# 03-_Power_Decoupling.net
KiCad netlist of a schematic drawn in Altium Designer
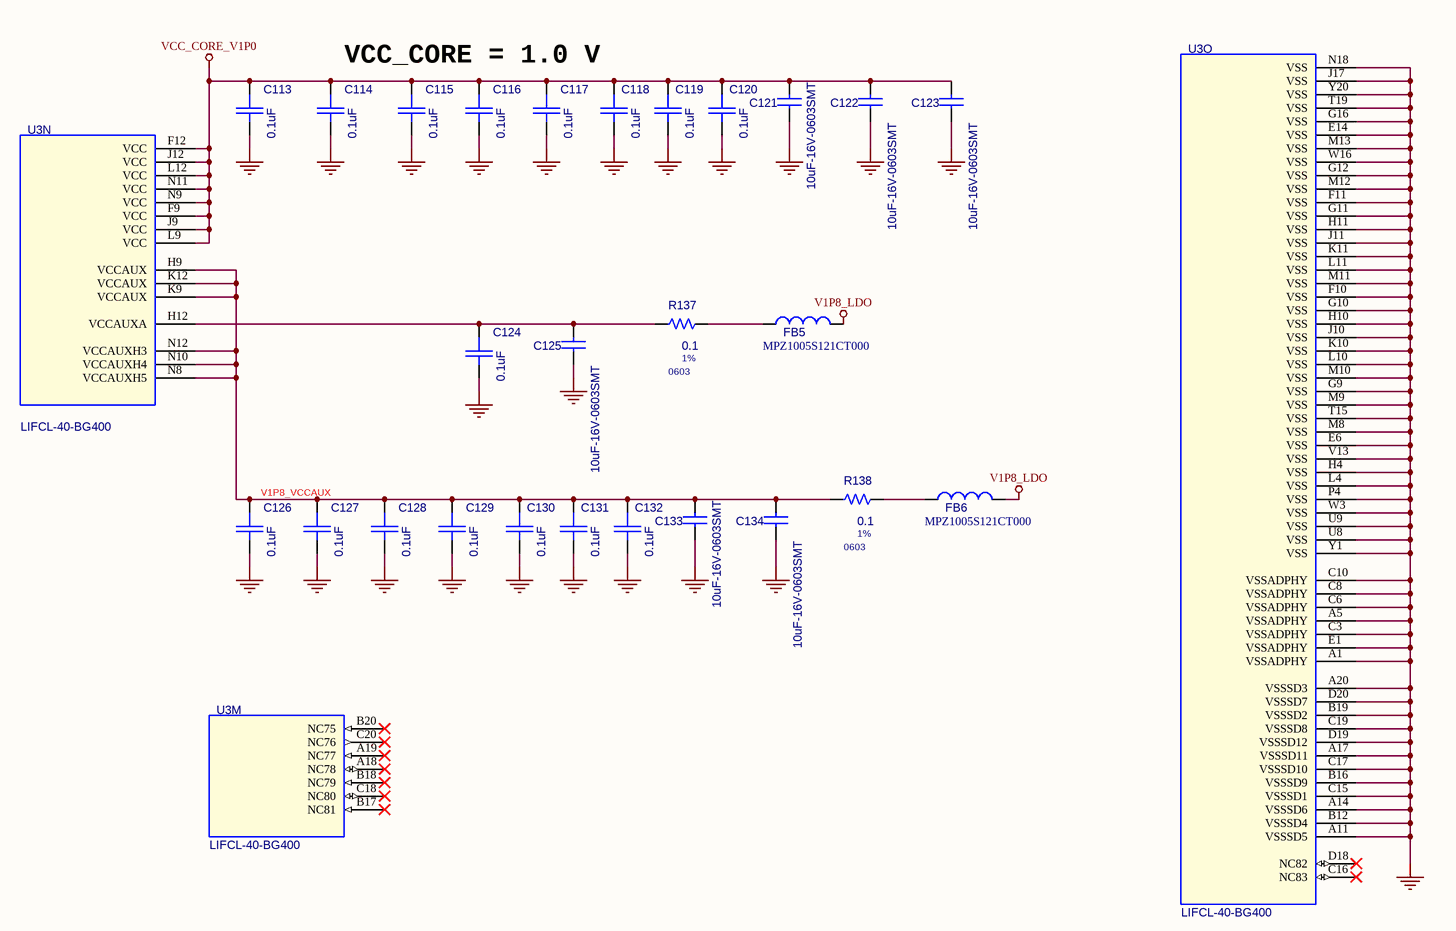
[diagram p0: 03- Power Decoupling.SchDoc]

(export (version "E")
  (design (tool "Eeschema 10.0.6"))
  (components
    (comp (ref "C113")
      (value "0.1uF")
      (footprint "C0201")
      (description "CAP CER 0.1UF 25V 10% X5R 0201")
      (fields
        (field (name "MANUFACTURER") "Murata")
        (field (name "MANUFACTURER PART NUMBER") "GRM033R61E104KE14J")
      )
      (libsource (lib "*") (part "CAP_1"))
    )
    (comp (ref "C114")
      (value "0.1uF")
      (footprint "C0201")
      (description "CAP CER 0.1UF 25V 10% X5R 0201")
      (fields
        (field (name "MANUFACTURER") "Murata")
        (field (name "MANUFACTURER PART NUMBER") "GRM033R61E104KE14J")
      )
      (libsource (lib "*") (part "CAP_1"))
    )
    (comp (ref "C115")
      (value "0.1uF")
      (footprint "C0201")
      (description "CAP CER 0.1UF 25V 10% X5R 0201")
      (fields
        (field (name "MANUFACTURER") "Murata")
        (field (name "MANUFACTURER PART NUMBER") "GRM033R61E104KE14J")
      )
      (libsource (lib "*") (part "CAP_1"))
    )
    (comp (ref "C116")
      (value "0.1uF")
      (footprint "C0201")
      (description "CAP CER 0.1UF 25V 10% X5R 0201")
      (fields
        (field (name "MANUFACTURER") "Murata")
        (field (name "MANUFACTURER PART NUMBER") "GRM033R61E104KE14J")
      )
      (libsource (lib "*") (part "CAP_1"))
    )
    (comp (ref "C117")
      (value "0.1uF")
      (footprint "C0201")
      (description "CAP CER 0.1UF 25V 10% X5R 0201")
      (fields
        (field (name "MANUFACTURER") "Murata")
        (field (name "MANUFACTURER PART NUMBER") "GRM033R61E104KE14J")
      )
      (libsource (lib "*") (part "CAP_1"))
    )
    (comp (ref "C118")
      (value "0.1uF")
      (footprint "C0201")
      (description "CAP CER 0.1UF 25V 10% X5R 0201")
      (fields
        (field (name "MANUFACTURER") "Murata")
        (field (name "MANUFACTURER PART NUMBER") "GRM033R61E104KE14J")
      )
      (libsource (lib "*") (part "CAP_SMT_0805"))
    )
    (comp (ref "C119")
      (value "0.1uF")
      (footprint "C0201")
      (description "CAP CER 0.1UF 25V 10% X5R 0201")
      (fields
        (field (name "MANUFACTURER") "Murata")
        (field (name "MANUFACTURER PART NUMBER") "GRM033R61E104KE14J")
      )
      (libsource (lib "*") (part "CAP_SMT_0805"))
    )
    (comp (ref "C120")
      (value "0.1uF")
      (footprint "C0201")
      (description "CAP CER 0.1UF 25V 10% X5R 0201")
      (fields
        (field (name "MANUFACTURER") "Murata")
        (field (name "MANUFACTURER PART NUMBER") "GRM033R61E104KE14J")
      )
      (libsource (lib "*") (part "CAP_SMT_0805"))
    )
    (comp (ref "C121")
      (value "10uF-16V-0603SMT")
      (footprint "C0603")
      (libsource (lib "*") (part "CAP NP_Dup1"))
    )
    (comp (ref "C122")
      (value "10uF-16V-0603SMT")
      (footprint "C0603")
      (libsource (lib "*") (part "CAP NP_Dup1"))
    )
    (comp (ref "C123")
      (value "10uF-16V-0603SMT")
      (footprint "C0603")
      (libsource (lib "*") (part "CAP NP_Dup1"))
    )
    (comp (ref "C124")
      (value "0.1uF")
      (footprint "C0201")
      (description "CAP CER 0.1UF 25V 10% X5R 0201")
      (fields
        (field (name "MANUFACTURER") "Murata")
        (field (name "MANUFACTURER PART NUMBER") "GRM033R61E104KE14J")
      )
      (libsource (lib "*") (part "CAP_1"))
    )
    (comp (ref "C125")
      (value "10uF-16V-0603SMT")
      (footprint "C0603")
      (libsource (lib "*") (part "CAP NP_Dup1"))
    )
    (comp (ref "C126")
      (value "0.1uF")
      (footprint "C0201")
      (description "CAP CER 0.1UF 25V 10% X5R 0201")
      (fields
        (field (name "MANUFACTURER") "Murata")
        (field (name "MANUFACTURER PART NUMBER") "GRM033R61E104KE14J")
      )
      (libsource (lib "*") (part "CAP_1"))
    )
    (comp (ref "C127")
      (value "0.1uF")
      (footprint "C0201")
      (description "CAP CER 0.1UF 25V 10% X5R 0201")
      (fields
        (field (name "MANUFACTURER") "Murata")
        (field (name "MANUFACTURER PART NUMBER") "GRM033R61E104KE14J")
      )
      (libsource (lib "*") (part "CAP_1"))
    )
    (comp (ref "C128")
      (value "0.1uF")
      (footprint "C0201")
      (description "CAP CER 0.1UF 25V 10% X5R 0201")
      (fields
        (field (name "MANUFACTURER PART NUMBER") "GRM033R61E104KE14J")
        (field (name "MANUFACTURER") "Murata")
      )
      (libsource (lib "*") (part "CAP_1"))
    )
    (comp (ref "C129")
      (value "0.1uF")
      (footprint "C0201")
      (description "CAP CER 0.1UF 25V 10% X5R 0201")
      (fields
        (field (name "MANUFACTURER") "Murata")
        (field (name "MANUFACTURER PART NUMBER") "GRM033R61E104KE14J")
      )
      (libsource (lib "*") (part "CAP_1"))
    )
    (comp (ref "C130")
      (value "0.1uF")
      (footprint "C0201")
      (description "CAP CER 0.1UF 25V 10% X5R 0201")
      (fields
        (field (name "MANUFACTURER") "Murata")
        (field (name "MANUFACTURER PART NUMBER") "GRM033R61E104KE14J")
      )
      (libsource (lib "*") (part "CAP_SMT_0805"))
    )
    (comp (ref "C131")
      (value "0.1uF")
      (footprint "C0201")
      (description "CAP CER 0.1UF 25V 10% X5R 0201")
      (fields
        (field (name "MANUFACTURER") "Murata")
        (field (name "MANUFACTURER PART NUMBER") "GRM033R61E104KE14J")
      )
      (libsource (lib "*") (part "CAP_SMT_0805"))
    )
    (comp (ref "C132")
      (value "0.1uF")
      (footprint "C0201")
      (description "CAP CER 0.1UF 25V 10% X5R 0201")
      (fields
        (field (name "MANUFACTURER") "Murata")
        (field (name "MANUFACTURER PART NUMBER") "GRM033R61E104KE14J")
      )
      (libsource (lib "*") (part "CAP_SMT_0805"))
    )
    (comp (ref "C133")
      (value "10uF-16V-0603SMT")
      (footprint "C0603")
      (libsource (lib "*") (part "CAP NP_Dup1"))
    )
    (comp (ref "C134")
      (value "10uF-16V-0603SMT")
      (footprint "C0603")
      (libsource (lib "*") (part "CAP NP_Dup1"))
    )
    (comp (ref "FB5")
      (value "MPZ1005S121CT000")
      (footprint "FB0402")
      (description "FERRITE BEAD 120 OHM 0402 1LN")
      (fields (field (name "MANUFACTURER") "TDK Corporation"))
      (libsource (lib "*") (part "INDUCTOR_0"))
    )
    (comp (ref "FB6")
      (value "MPZ1005S121CT000")
      (footprint "FB0402")
      (description "FERRITE BEAD 120 OHM 0402 1LN")
      (fields (field (name "MANUFACTURER") "TDK Corporation"))
      (libsource (lib "*") (part "INDUCTOR_0"))
    )
    (comp (ref "R137")
      (value "0.1")
      (footprint "0603")
      (fields
        (field (name "VOLTAGE") "RVMAX")
        (field (name "POWER") "RMAX")
        (field (name "TOLLERANCE") "1%")
        (field (name "PCB FOOTPRINT") "0603")
      )
      (libsource (lib "*") (part "R_Dup2"))
    )
    (comp (ref "R138")
      (value "0.1")
      (footprint "0603")
      (fields
        (field (name "VOLTAGE") "RVMAX")
        (field (name "POWER") "RMAX")
        (field (name "TOLLERANCE") "1%")
        (field (name "PCB FOOTPRINT") "0603")
      )
      (libsource (lib "*") (part "R_Dup2"))
    )
    (comp (ref "U3")
      (value "LIFCL-40-BG400")
      (footprint "LIFCL-40-BG400")
      (libsource (lib "*") (part "LIFCL-40-BG400"))
    )
  )
  (nets
    (net (code "1") (name "/V1P8_VCCAUX") (class "Default")
      (node (ref "C126") (pin "1") (pinfunction "1_1") (pintype "passive"))
      (node (ref "C127") (pin "1") (pinfunction "1_1") (pintype "passive"))
      (node (ref "C128") (pin "1") (pinfunction "1_1") (pintype "passive"))
      (node (ref "C129") (pin "1") (pinfunction "1_1") (pintype "passive"))
      (node (ref "C130") (pin "1") (pinfunction "1_1") (pintype "passive"))
      (node (ref "C131") (pin "1") (pinfunction "1_1") (pintype "passive"))
      (node (ref "C132") (pin "1") (pinfunction "1_1") (pintype "passive"))
      (node (ref "C133") (pin "2") (pinfunction "2_2") (pintype "passive"))
      (node (ref "C134") (pin "2") (pinfunction "2_2") (pintype "passive"))
      (node (ref "R138") (pin "1") (pinfunction "1_1") (pintype "passive"))
      (node (ref "U3") (pin "H9") (pinfunction "VCCAUX_H9") (pintype "power_in"))
      (node (ref "U3") (pin "K12") (pinfunction "VCCAUX_K12") (pintype "power_in"))
      (node (ref "U3") (pin "K9") (pinfunction "VCCAUX_K9") (pintype "power_in"))
      (node (ref "U3") (pin "N10") (pinfunction "VCCAUXH4_N10") (pintype "power_in"))
      (node (ref "U3") (pin "N12") (pinfunction "VCCAUXH3_N12") (pintype "power_in"))
      (node (ref "U3") (pin "N8") (pinfunction "VCCAUXH5_N8") (pintype "power_in"))
    )
    (net (code "2") (name "GND") (class "Default")
      (node (ref "C113") (pin "2") (pinfunction "2_2") (pintype "passive"))
      (node (ref "C114") (pin "2") (pinfunction "2_2") (pintype "passive"))
      (node (ref "C115") (pin "2") (pinfunction "2_2") (pintype "passive"))
      (node (ref "C116") (pin "2") (pinfunction "2_2") (pintype "passive"))
      (node (ref "C117") (pin "2") (pinfunction "2_2") (pintype "passive"))
      (node (ref "C118") (pin "2") (pinfunction "2_2") (pintype "passive"))
      (node (ref "C119") (pin "2") (pinfunction "2_2") (pintype "passive"))
      (node (ref "C120") (pin "2") (pinfunction "2_2") (pintype "passive"))
      (node (ref "C121") (pin "1") (pinfunction "1_1") (pintype "passive"))
      (node (ref "C122") (pin "1") (pinfunction "1_1") (pintype "passive"))
      (node (ref "C123") (pin "1") (pinfunction "1_1") (pintype "passive"))
      (node (ref "C124") (pin "2") (pinfunction "2_2") (pintype "passive"))
      (node (ref "C125") (pin "1") (pinfunction "1_1") (pintype "passive"))
      (node (ref "C126") (pin "2") (pinfunction "2_2") (pintype "passive"))
      (node (ref "C127") (pin "2") (pinfunction "2_2") (pintype "passive"))
      (node (ref "C128") (pin "2") (pinfunction "2_2") (pintype "passive"))
      (node (ref "C129") (pin "2") (pinfunction "2_2") (pintype "passive"))
      (node (ref "C130") (pin "2") (pinfunction "2_2") (pintype "passive"))
      (node (ref "C131") (pin "2") (pinfunction "2_2") (pintype "passive"))
      (node (ref "C132") (pin "2") (pinfunction "2_2") (pintype "passive"))
      (node (ref "C133") (pin "1") (pinfunction "1_1") (pintype "passive"))
      (node (ref "C134") (pin "1") (pinfunction "1_1") (pintype "passive"))
      (node (ref "U3") (pin "A1") (pinfunction "VSSADPHY_A1") (pintype "power_in"))
      (node (ref "U3") (pin "A11") (pinfunction "VSSSD5_A11") (pintype "power_in"))
      (node (ref "U3") (pin "A14") (pinfunction "VSSSD6_A14") (pintype "power_in"))
      (node (ref "U3") (pin "A17") (pinfunction "VSSSD11_A17") (pintype "passive"))
      (node (ref "U3") (pin "A20") (pinfunction "VSSSD3_A20") (pintype "power_in"))
      (node (ref "U3") (pin "A5") (pinfunction "VSSADPHY_A5") (pintype "power_in"))
      (node (ref "U3") (pin "B12") (pinfunction "VSSSD4_B12") (pintype "power_in"))
      (node (ref "U3") (pin "B16") (pinfunction "VSSSD9_B16") (pintype "passive"))
      (node (ref "U3") (pin "B19") (pinfunction "VSSSD2_B19") (pintype "power_in"))
      (node (ref "U3") (pin "C10") (pinfunction "VSSADPHY_C10") (pintype "power_in"))
      (node (ref "U3") (pin "C15") (pinfunction "VSSSD1_C15") (pintype "power_in"))
      (node (ref "U3") (pin "C17") (pinfunction "VSSSD10_C17") (pintype "passive"))
      (node (ref "U3") (pin "C19") (pinfunction "VSSSD8_C19") (pintype "passive"))
      (node (ref "U3") (pin "C3") (pinfunction "VSSADPHY_C3") (pintype "power_in"))
      (node (ref "U3") (pin "C6") (pinfunction "VSSADPHY_C6") (pintype "power_in"))
      (node (ref "U3") (pin "C8") (pinfunction "VSSADPHY_C8") (pintype "power_in"))
      (node (ref "U3") (pin "D19") (pinfunction "VSSSD12_D19") (pintype "passive"))
      (node (ref "U3") (pin "D20") (pinfunction "VSSSD7_D20") (pintype "passive"))
      (node (ref "U3") (pin "E1") (pinfunction "VSSADPHY_E1") (pintype "power_in"))
      (node (ref "U3") (pin "E14") (pinfunction "VSS_E14") (pintype "power_in"))
      (node (ref "U3") (pin "E6") (pinfunction "VSS_E6") (pintype "power_in"))
      (node (ref "U3") (pin "F10") (pinfunction "VSS_F10") (pintype "power_in"))
      (node (ref "U3") (pin "F11") (pinfunction "VSS_F11") (pintype "power_in"))
      (node (ref "U3") (pin "G10") (pinfunction "VSS_G10") (pintype "power_in"))
      (node (ref "U3") (pin "G11") (pinfunction "VSS_G11") (pintype "power_in"))
      (node (ref "U3") (pin "G12") (pinfunction "VSS_G12") (pintype "power_in"))
      (node (ref "U3") (pin "G16") (pinfunction "VSS_G16") (pintype "power_in"))
      (node (ref "U3") (pin "G9") (pinfunction "VSS_G9") (pintype "power_in"))
      (node (ref "U3") (pin "H10") (pinfunction "VSS_H10") (pintype "power_in"))
      (node (ref "U3") (pin "H11") (pinfunction "VSS_H11") (pintype "power_in"))
      (node (ref "U3") (pin "H4") (pinfunction "VSS_H4") (pintype "power_in"))
      (node (ref "U3") (pin "J10") (pinfunction "VSS_J10") (pintype "power_in"))
      (node (ref "U3") (pin "J11") (pinfunction "VSS_J11") (pintype "power_in"))
      (node (ref "U3") (pin "J17") (pinfunction "VSS_J17") (pintype "power_in"))
      (node (ref "U3") (pin "K10") (pinfunction "VSS_K10") (pintype "power_in"))
      (node (ref "U3") (pin "K11") (pinfunction "VSS_K11") (pintype "power_in"))
      (node (ref "U3") (pin "L10") (pinfunction "VSS_L10") (pintype "power_in"))
      (node (ref "U3") (pin "L11") (pinfunction "VSS_L11") (pintype "power_in"))
      (node (ref "U3") (pin "L4") (pinfunction "VSS_L4") (pintype "power_in"))
      (node (ref "U3") (pin "M10") (pinfunction "VSS_M10") (pintype "power_in"))
      (node (ref "U3") (pin "M11") (pinfunction "VSS_M11") (pintype "power_in"))
      (node (ref "U3") (pin "M12") (pinfunction "VSS_M12") (pintype "power_in"))
      (node (ref "U3") (pin "M13") (pinfunction "VSS_M13") (pintype "power_in"))
      (node (ref "U3") (pin "M8") (pinfunction "VSS_M8") (pintype "power_in"))
      (node (ref "U3") (pin "M9") (pinfunction "VSS_M9") (pintype "power_in"))
      (node (ref "U3") (pin "N18") (pinfunction "VSS_N18") (pintype "power_in"))
      (node (ref "U3") (pin "P4") (pinfunction "VSS_P4") (pintype "power_in"))
      (node (ref "U3") (pin "T15") (pinfunction "VSS_T15") (pintype "power_in"))
      (node (ref "U3") (pin "T19") (pinfunction "VSS_T19") (pintype "power_in"))
      (node (ref "U3") (pin "U8") (pinfunction "VSS_U8") (pintype "power_in"))
      (node (ref "U3") (pin "U9") (pinfunction "VSS_U9") (pintype "power_in"))
      (node (ref "U3") (pin "V13") (pinfunction "VSS_V13") (pintype "power_in"))
      (node (ref "U3") (pin "W16") (pinfunction "VSS_W16") (pintype "power_in"))
      (node (ref "U3") (pin "W3") (pinfunction "VSS_W3") (pintype "power_in"))
      (node (ref "U3") (pin "Y1") (pinfunction "VSS_Y1") (pintype "power_in"))
      (node (ref "U3") (pin "Y20") (pinfunction "VSS_Y20") (pintype "power_in"))
    )
    (net (code "3") (name "Net-(FB5-Pad1)") (class "Default")
      (node (ref "FB5") (pin "1") (pinfunction "1_1") (pintype "passive"))
      (node (ref "R137") (pin "2") (pinfunction "2_2") (pintype "passive"))
    )
    (net (code "4") (name "Net-(FB6-Pad1)") (class "Default")
      (node (ref "FB6") (pin "1") (pinfunction "1_1") (pintype "passive"))
      (node (ref "R138") (pin "2") (pinfunction "2_2") (pintype "passive"))
    )
    (net (code "5") (name "Net-(U3N-VCCAUXA)") (class "Default")
      (node (ref "C124") (pin "1") (pinfunction "1_1") (pintype "passive"))
      (node (ref "C125") (pin "2") (pinfunction "2_2") (pintype "passive"))
      (node (ref "R137") (pin "1") (pinfunction "1_1") (pintype "passive"))
      (node (ref "U3") (pin "H12") (pinfunction "VCCAUXA_H12") (pintype "power_in"))
    )
    (net (code "6") (name "V1P8_LDO") (class "Default")
      (node (ref "FB5") (pin "2") (pinfunction "2_2") (pintype "passive"))
      (node (ref "FB6") (pin "2") (pinfunction "2_2") (pintype "passive"))
    )
    (net (code "7") (name "VCC_CORE_V1P0") (class "Default")
      (node (ref "C113") (pin "1") (pinfunction "1_1") (pintype "passive"))
      (node (ref "C114") (pin "1") (pinfunction "1_1") (pintype "passive"))
      (node (ref "C115") (pin "1") (pinfunction "1_1") (pintype "passive"))
      (node (ref "C116") (pin "1") (pinfunction "1_1") (pintype "passive"))
      (node (ref "C117") (pin "1") (pinfunction "1_1") (pintype "passive"))
      (node (ref "C118") (pin "1") (pinfunction "1_1") (pintype "passive"))
      (node (ref "C119") (pin "1") (pinfunction "1_1") (pintype "passive"))
      (node (ref "C120") (pin "1") (pinfunction "1_1") (pintype "passive"))
      (node (ref "C121") (pin "2") (pinfunction "2_2") (pintype "passive"))
      (node (ref "C122") (pin "2") (pinfunction "2_2") (pintype "passive"))
      (node (ref "C123") (pin "2") (pinfunction "2_2") (pintype "passive"))
      (node (ref "U3") (pin "F12") (pinfunction "VCC_F12") (pintype "power_in"))
      (node (ref "U3") (pin "F9") (pinfunction "VCC_F9") (pintype "power_in"))
      (node (ref "U3") (pin "J12") (pinfunction "VCC_J12") (pintype "power_in"))
      (node (ref "U3") (pin "J9") (pinfunction "VCC_J9") (pintype "power_in"))
      (node (ref "U3") (pin "L12") (pinfunction "VCC_L12") (pintype "power_in"))
      (node (ref "U3") (pin "L9") (pinfunction "VCC_L9") (pintype "power_in"))
      (node (ref "U3") (pin "N11") (pinfunction "VCC_N11") (pintype "power_in"))
      (node (ref "U3") (pin "N9") (pinfunction "VCC_N9") (pintype "power_in"))
    )
    (net (code "8") (name "unconnected-(U3M-NC75-PadB20)") (class "Default")
      (node (ref "U3") (pin "B20") (pinfunction "NC75_B20") (pintype "input+no_connect"))
    )
    (net (code "9") (name "unconnected-(U3M-NC76-PadC20)") (class "Default")
      (node (ref "U3") (pin "C20") (pinfunction "NC76_C20") (pintype "output+no_connect"))
    )
    (net (code "10") (name "unconnected-(U3M-NC77-PadA19)") (class "Default")
      (node (ref "U3") (pin "A19") (pinfunction "NC77_A19") (pintype "input+no_connect"))
    )
    (net (code "11") (name "unconnected-(U3M-NC78-PadA18)") (class "Default")
      (node (ref "U3") (pin "A18") (pinfunction "NC78_A18") (pintype "bidirectional+no_connect"))
    )
    (net (code "12") (name "unconnected-(U3M-NC79-PadB18)") (class "Default")
      (node (ref "U3") (pin "B18") (pinfunction "NC79_B18") (pintype "input+no_connect"))
    )
    (net (code "13") (name "unconnected-(U3M-NC80-PadC18)") (class "Default")
      (node (ref "U3") (pin "C18") (pinfunction "NC80_C18") (pintype "bidirectional+no_connect"))
    )
    (net (code "14") (name "unconnected-(U3M-NC81-PadB17)") (class "Default")
      (node (ref "U3") (pin "B17") (pinfunction "NC81_B17") (pintype "input+no_connect"))
    )
    (net (code "15") (name "unconnected-(U3O-NC82-PadD18)") (class "Default")
      (node (ref "U3") (pin "D18") (pinfunction "NC82_D18") (pintype "bidirectional+no_connect"))
    )
    (net (code "16") (name "unconnected-(U3O-NC83-PadC16)") (class "Default")
      (node (ref "U3") (pin "C16") (pinfunction "NC83_C16") (pintype "bidirectional+no_connect"))
    )
  )
)
